# MCU.net
KiCad netlist of a schematic drawn in Altium Designer
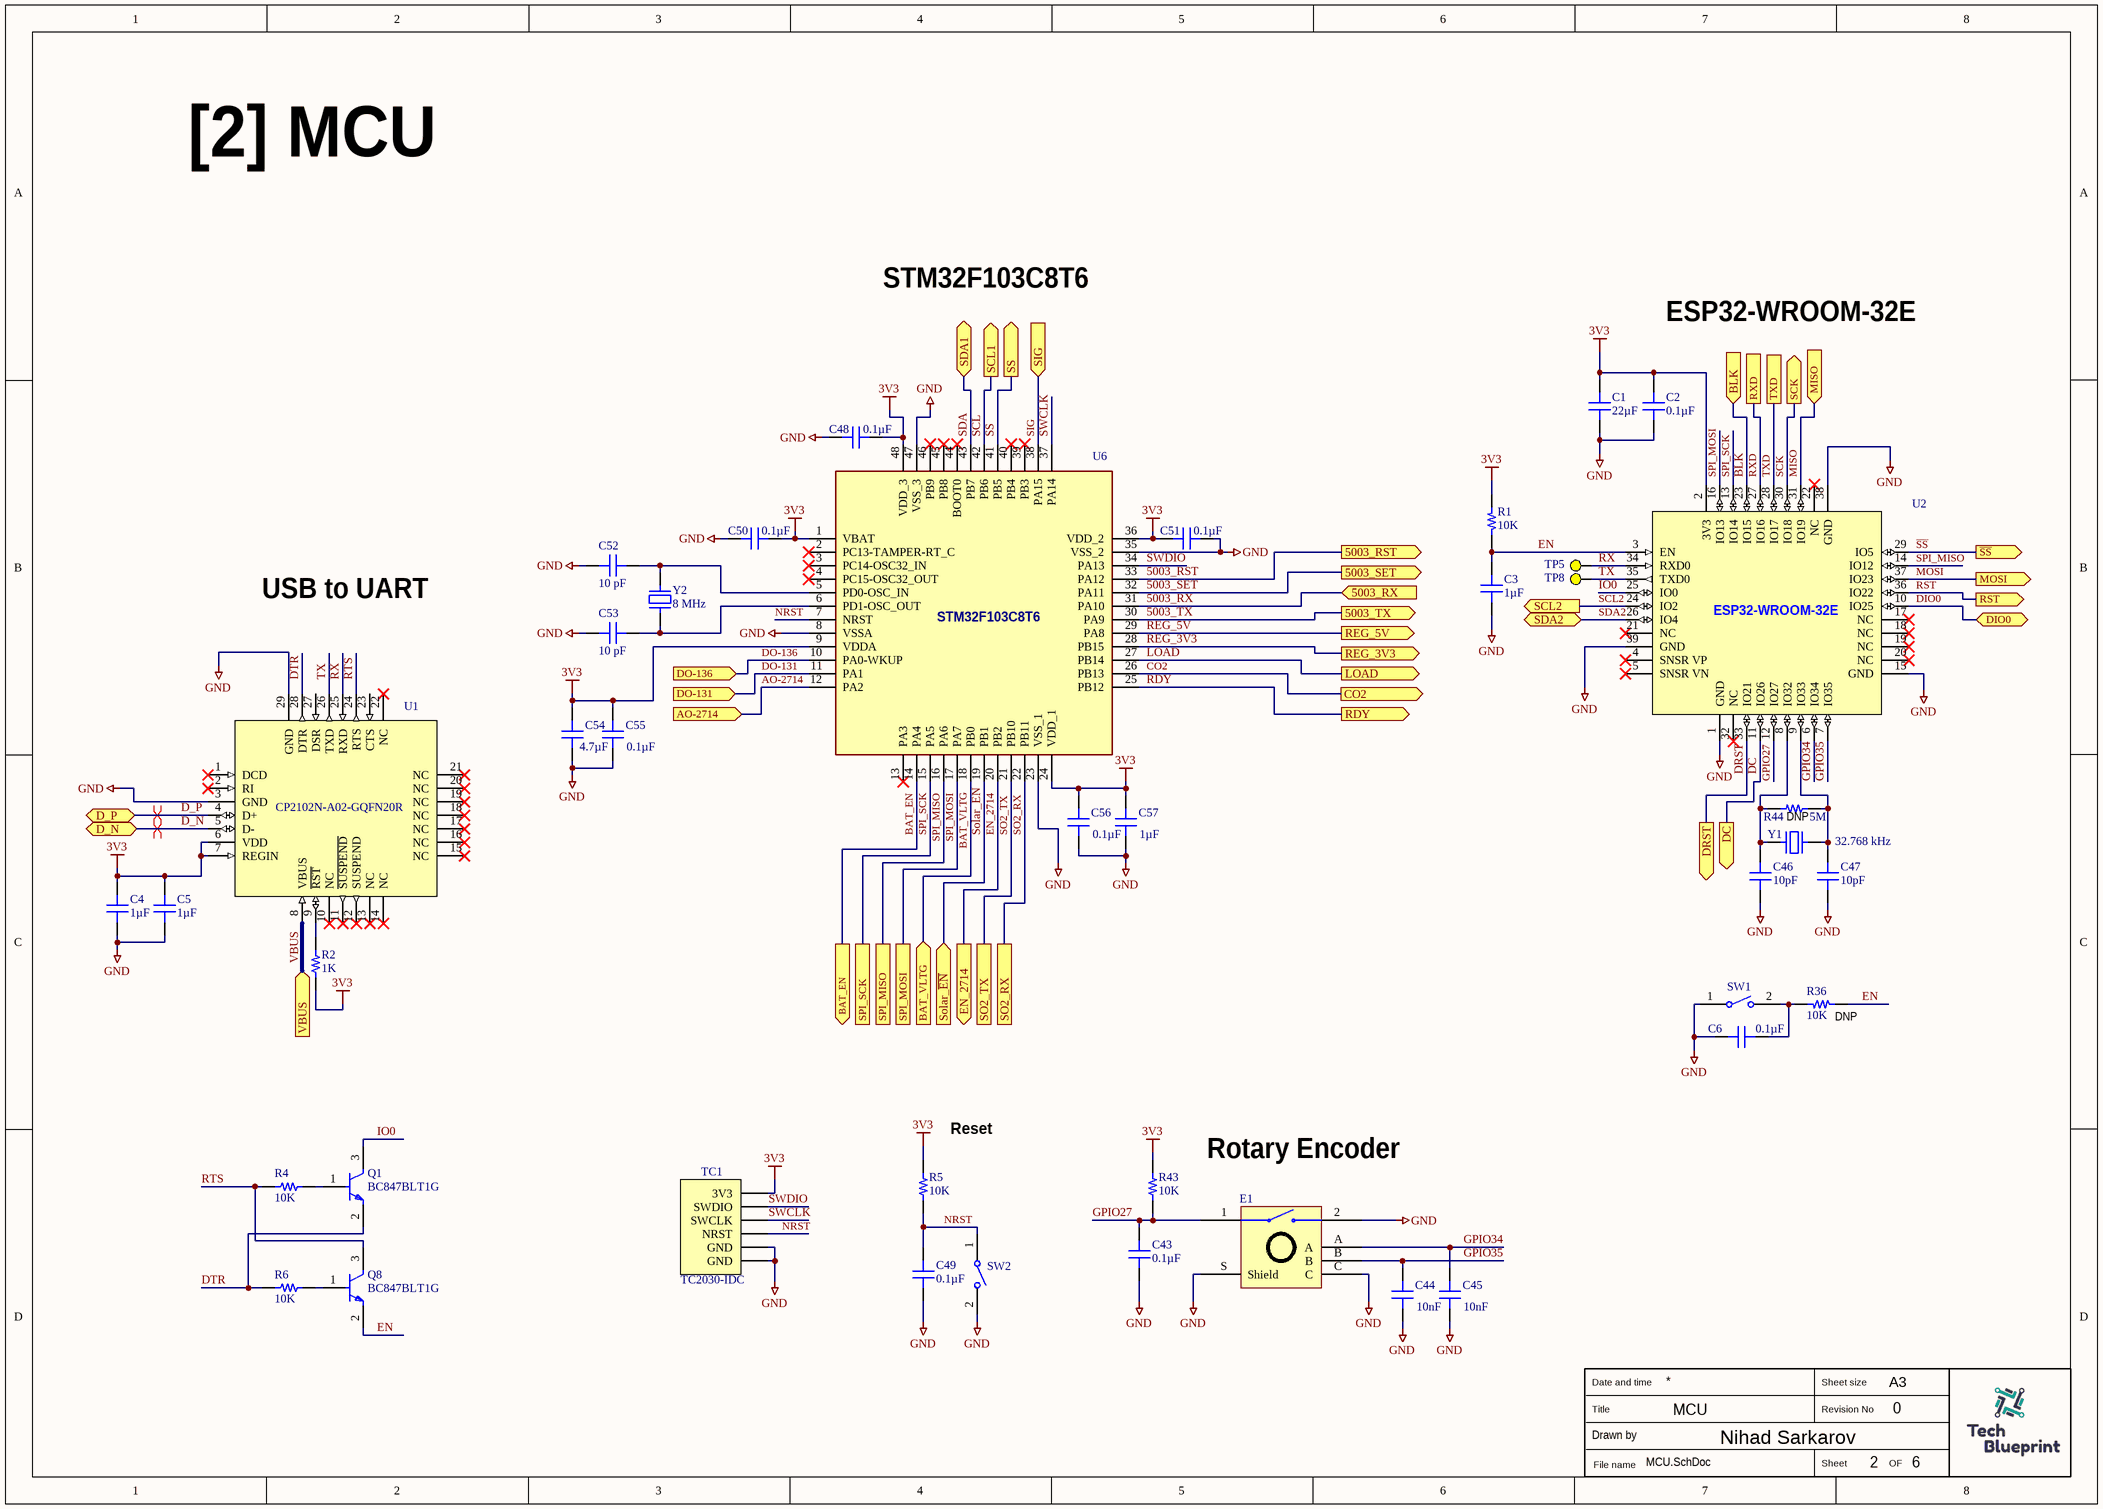
[diagram p0: MCU.SchDoc]

(export (version "E")
  (design (tool "Eeschema 10.0.6"))
  (components
    (comp (ref "C1")
      (value "22µF")
      (footprint "CAP 0805_2012")
      (description "CAP CER 22UF 6.3V X5R 0805")
      (fields
        (field (name "PART NUMBER") "08056D226KAT2A")
        (field (name "CAPACITANCE") "22µF")
        (field (name "MANUFACTURER") "AVX Corporation")
      )
      (libsource (lib "Celestial Altium Library - altium_library") (part "Capacitor"))
    )
    (comp (ref "C2")
      (value "0.1µF")
      (footprint "CAP 0805_2012")
      (description "CAP CER 0.1UF 25V X7R 0805")
      (fields
        (field (name "PART NUMBER") "08053C104KAT4A")
        (field (name "CAPACITANCE") "0.1µF")
        (field (name "MANUFACTURER") "AVX Corporation")
      )
      (libsource (lib "Celestial Altium Library - altium_library") (part "Capacitor"))
    )
    (comp (ref "C3")
      (value "1µF")
      (footprint "CAP 0805_2012")
      (description "CAP CER 1UF 6.3V X5R 0805")
      (fields
        (field (name "PART NUMBER") "LGC26D105MAT2S1")
        (field (name "CAPACITANCE") "1µF")
        (field (name "MANUFACTURER") "AVX Corporation")
      )
      (libsource (lib "Celestial Altium Library - altium_library") (part "Capacitor"))
    )
    (comp (ref "C4")
      (value "1µF")
      (footprint "CAP 0805_2012")
      (description "CAP CER 1UF 6.3V X5R 0805")
      (fields
        (field (name "PART NUMBER") "LGC26D105MAT2S1")
        (field (name "CAPACITANCE") "1µF")
        (field (name "MANUFACTURER") "AVX Corporation")
      )
      (libsource (lib "Celestial Altium Library - altium_library") (part "Capacitor"))
    )
    (comp (ref "C5")
      (value "1µF")
      (footprint "CAP 0805_2012")
      (description "CAP CER 1UF 6.3V X5R 0805")
      (fields
        (field (name "PART NUMBER") "LGC26D105MAT2S1")
        (field (name "CAPACITANCE") "1µF")
        (field (name "MANUFACTURER") "AVX Corporation")
      )
      (libsource (lib "Celestial Altium Library - altium_library") (part "Capacitor"))
    )
    (comp (ref "C6")
      (value "0.1µF")
      (footprint "CAP 0805_2012")
      (description "CAP CER 0.1UF 25V X7R 0805")
      (fields
        (field (name "PART NUMBER") "08053C104KAT4A")
        (field (name "CAPACITANCE") "0.1µF")
        (field (name "MANUFACTURER") "AVX Corporation")
      )
      (libsource (lib "Celestial Altium Library - altium_library") (part "Capacitor"))
    )
    (comp (ref "C43")
      (value "0.1µF")
      (footprint "CAP 0603_1608")
      (description "CAP CER 0.1UF 25V X7R 0603")
      (fields
        (field (name "PART NUMBER") "06033C104K4T4A")
        (field (name "CAPACITANCE") "0.1µF")
        (field (name "MANUFACTURER") "AVX Corporation")
      )
      (libsource (lib "Celestial Altium Library - altium_library") (part "Capacitor"))
    )
    (comp (ref "C44")
      (value "10000 pF")
      (footprint "CAP 0603_1608")
      (description "CAP CER 0603 10NF 16V X7R 10%")
      (fields
        (field (name "PART NUMBER") "C0603C103K4RECAUTO")
        (field (name "CAPACITANCE") "10nF")
        (field (name "MANUFACTURER") "KEMET")
      )
      (libsource (lib "Celestial Altium Library - altium_library") (part "Capacitor"))
    )
    (comp (ref "C45")
      (value "10000 pF")
      (footprint "CAP 0603_1608")
      (description "CAP CER 0603 10NF 16V X7R 10%")
      (fields
        (field (name "PART NUMBER") "C0603C103K4RECAUTO")
        (field (name "CAPACITANCE") "10nF")
        (field (name "MANUFACTURER") "KEMET")
      )
      (libsource (lib "Celestial Altium Library - altium_library") (part "Capacitor"))
    )
    (comp (ref "C46")
      (value "10pF")
      (footprint "CAP 0603_1608")
      (description "CAP CER 10PF 50V NP0 0603")
      (fields
        (field (name "PART NUMBER") "06035A100J4T2A")
        (field (name "CAPACITANCE") "10pF")
        (field (name "MANUFACTURER") "AVX Corporation")
      )
      (libsource (lib "Celestial Altium Library - altium_library") (part "Capacitor"))
    )
    (comp (ref "C47")
      (value "10pF")
      (footprint "CAP 0603_1608")
      (description "CAP CER 10PF 50V NP0 0603")
      (fields
        (field (name "PART NUMBER") "06035A100J4T2A")
        (field (name "CAPACITANCE") "10pF")
        (field (name "MANUFACTURER") "AVX Corporation")
      )
      (libsource (lib "Celestial Altium Library - altium_library") (part "Capacitor"))
    )
    (comp (ref "C48")
      (value "0.1µF")
      (footprint "CAP 0805_2012")
      (description "CAP CER 0.1UF 25V X7R 0805")
      (fields
        (field (name "PART NUMBER") "08053C104K4Z2A")
        (field (name "CAPACITANCE") "0.1µF")
        (field (name "MANUFACTURER") "AVX Corporation")
      )
      (libsource (lib "Celestial Altium Library - altium_library") (part "Capacitor"))
    )
    (comp (ref "C49")
      (value "0.1µF")
      (footprint "CAP 0603_1608")
      (description "CAP CER 0.1UF 25V X7R 0603")
      (fields
        (field (name "PART NUMBER") "06033C104K4T4A")
        (field (name "CAPACITANCE") "0.1µF")
        (field (name "MANUFACTURER") "AVX Corporation")
      )
      (libsource (lib "Celestial Altium Library - altium_library") (part "Capacitor"))
    )
    (comp (ref "C50")
      (value "0.1µF")
      (footprint "CAP 0805_2012")
      (description "CAP CER 0.1UF 25V X7R 0805")
      (fields
        (field (name "PART NUMBER") "08053C104K4Z2A")
        (field (name "CAPACITANCE") "0.1µF")
        (field (name "MANUFACTURER") "AVX Corporation")
      )
      (libsource (lib "Celestial Altium Library - altium_library") (part "Capacitor"))
    )
    (comp (ref "C51")
      (value "0.1µF")
      (footprint "CAP 0805_2012")
      (description "CAP CER 0.1UF 25V X7R 0805")
      (fields
        (field (name "PART NUMBER") "08053C104K4Z2A")
        (field (name "CAPACITANCE") "0.1µF")
        (field (name "MANUFACTURER") "AVX Corporation")
      )
      (libsource (lib "Celestial Altium Library - altium_library") (part "Capacitor"))
    )
    (comp (ref "C52")
      (value "10 pF")
      (footprint "CAP 0603_1608")
      (description "CAP CER 10PF 50V C0G/NP0 0603")
      (fields
        (field (name "PART NUMBER") "500X14N100MV4T")
        (field (name "CAPACITANCE") "10 pF")
        (field (name "MANUFACTURER") "Johanson Dielectrics Inc.")
      )
      (libsource (lib "Celestial Altium Library - altium_library") (part "Capacitor"))
    )
    (comp (ref "C53")
      (value "10 pF")
      (footprint "CAP 0603_1608")
      (description "CAP CER 10PF 50V C0G/NP0 0603")
      (fields
        (field (name "PART NUMBER") "500X14N100MV4T")
        (field (name "CAPACITANCE") "10 pF")
        (field (name "MANUFACTURER") "Johanson Dielectrics Inc.")
      )
      (libsource (lib "Celestial Altium Library - altium_library") (part "Capacitor"))
    )
    (comp (ref "C54")
      (value "4.7µF")
      (footprint "CAP 0805_2012")
      (description "CAP CER 4.7UF 10V X5R 0805")
      (fields
        (field (name "PART NUMBER") "0805ZD475KAT2A")
        (field (name "CAPACITANCE") "4.7µF")
        (field (name "MANUFACTURER") "AVX Corporation")
      )
      (libsource (lib "Celestial Altium Library - altium_library") (part "Capacitor"))
    )
    (comp (ref "C55")
      (value "0.1µF")
      (footprint "CAP 0805_2012")
      (description "CAP CER 0.1UF 25V X7R 0805")
      (fields
        (field (name "PART NUMBER") "08053C104K4Z2A")
        (field (name "CAPACITANCE") "0.1µF")
        (field (name "MANUFACTURER") "AVX Corporation")
      )
      (libsource (lib "Celestial Altium Library - altium_library") (part "Capacitor"))
    )
    (comp (ref "C56")
      (value "0.1µF")
      (footprint "CAP 0805_2012")
      (description "CAP CER 0.1UF 25V X7R 0805")
      (fields
        (field (name "PART NUMBER") "08053C104K4Z2A")
        (field (name "CAPACITANCE") "0.1µF")
        (field (name "MANUFACTURER") "AVX Corporation")
      )
      (libsource (lib "Celestial Altium Library - altium_library") (part "Capacitor"))
    )
    (comp (ref "C57")
      (value "1µF")
      (footprint "CAP 0805_2012")
      (description "CAP CER 1UF 10V X7R 0805")
      (fields
        (field (name "PART NUMBER") "MM05ZC105KCZ2A")
        (field (name "CAPACITANCE") "1µF")
        (field (name "MANUFACTURER") "AVX Corporation")
      )
      (libsource (lib "Celestial Altium Library - altium_library") (part "Capacitor"))
    )
    (comp (ref "E1")
      (value "PEC11R-4315F-S0012")
      (footprint "BOURNS PEC11R-4315F-S0012")
      (description "ROTARY ENCODER MECHANICAL 12PPR")
      (fields (field (name "MANUFACTURER") "Bourns Inc."))
      (libsource (lib "Celestial Altium Library - altium_library") (part "BOURNS PEC11R-4315F-S0012"))
    )
    (comp (ref "Q1")
      (value "BC847BLT1G")
      (footprint "ON_Semi_318-08_MFG")
      (libsource (lib "Altium Content Vault") (part "BC847BLT1G"))
    )
    (comp (ref "Q8")
      (value "BC847BLT1G")
      (footprint "ON_Semi_318-08_MFG")
      (libsource (lib "Altium Content Vault") (part "BC847BLT1G"))
    )
    (comp (ref "R1")
      (value "10K")
      (footprint "RES 0805_2012")
      (description "RES SMD 10K OHM 5% 1/3W 0805")
      (fields
        (field (name "PART NUMBER") "CRGH0805J10K")
        (field (name "MANUFACTURER") "TE Connectivity Passive Product")
      )
      (libsource (lib "Celestial Altium Library - altium_library") (part "Resistor"))
    )
    (comp (ref "R2")
      (value "1K")
      (footprint "RES 0805_2012")
      (description "RES SMD 1K OHM 5% 1/3W 0805")
      (fields
        (field (name "PART NUMBER") "CRGH0805J1K0")
        (field (name "MANUFACTURER") "TE Connectivity Passive Product")
      )
      (libsource (lib "Celestial Altium Library - altium_library") (part "Resistor"))
    )
    (comp (ref "R4")
      (value "10K")
      (footprint "RES 0603_1608")
      (description "RES SMD 10K OHM 5% 1/10W 0603")
      (fields (field (name "PART NUMBER") "CRCW060310K0JNEA") (field (name "MANUFACTURER") "Vishay Dale"))
      (libsource (lib "Celestial Altium Library - altium_library") (part "Resistor"))
    )
    (comp (ref "R5")
      (value "10K")
      (footprint "RES 0603_1608")
      (description "RES SMD 10K OHM 5% 1/10W 0603")
      (fields (field (name "PART NUMBER") "CRCW060310K0JNEA") (field (name "MANUFACTURER") "Vishay Dale"))
      (libsource (lib "Celestial Altium Library - altium_library") (part "Resistor"))
    )
    (comp (ref "R6")
      (value "10K")
      (footprint "RES 0603_1608")
      (description "RES SMD 10K OHM 5% 1/10W 0603")
      (fields (field (name "PART NUMBER") "CRCW060310K0JNEA") (field (name "MANUFACTURER") "Vishay Dale"))
      (libsource (lib "Celestial Altium Library - altium_library") (part "Resistor"))
    )
    (comp (ref "R36")
      (value "10K")
      (footprint "RES 0805_2012")
      (description "RES SMD 10K OHM 5% 1/3W 0805")
      (fields
        (field (name "PART NUMBER") "CRGH0805J10K")
        (field (name "MANUFACTURER") "TE Connectivity Passive Product")
      )
      (libsource (lib "Celestial Altium Library - altium_library") (part "Resistor"))
    )
    (comp (ref "R43")
      (value "10K")
      (footprint "RES 0603_1608")
      (description "RES SMD 10K OHM 5% 1/10W 0603")
      (fields (field (name "PART NUMBER") "CRCW060310K0JNEA") (field (name "MANUFACTURER") "Vishay Dale"))
      (libsource (lib "Celestial Altium Library - altium_library") (part "Resistor"))
    )
    (comp (ref "R44")
      (value "5M")
      (footprint "RES 0603_1608")
      (description "RES SMD 5M OHM 1% 1/10W 0603")
      (fields (field (name "PART NUMBER") "HVC0603T5004FET") (field (name "MANUFACTURER") "Ohmite"))
      (libsource (lib "Celestial Altium Library - altium_library") (part "Resistor"))
    )
    (comp (ref "SW1")
      (value "FSMSMTR")
      (footprint "TECO-FSMSMTR_V")
      (description "FSMSM Push Button Switch, 50 mA, -35 to 85 degC, 2-Pin SMD, RoHS, Tape and Reel")
      (fields (field (name "MANUFACTURER") "TE Connectivity"))
      (libsource (lib "Schlib1") (part "CMP-2000-07501-1"))
    )
    (comp (ref "SW2")
      (value "FSMSMTR")
      (footprint "TECO-FSMSMTR_V")
      (description "FSMSM Push Button Switch, 50 mA, -35 to 85 degC, 2-Pin SMD, RoHS, Tape and Reel")
      (fields (field (name "MANUFACTURER") "TE Connectivity"))
      (libsource (lib "Altium Content Vault") (part "SW-SPST-2_C"))
    )
    (comp (ref "TC1")
      (value "TC2030-IDC")
      (footprint "TC2030-IDC")
      (description "PLUG-OF-NAILS 6-PIN W/ LEGS 8")
      (fields (field (name "MF") "Tag-Connect LLC"))
      (libsource (lib "Schlib1") (part "TC2030-IDC"))
    )
    (comp (ref "TP5")
      (value "Test point")
      (footprint "Test point")
      (description "1mm x 1mm round pad for testing purposes")
      (libsource (lib "Schlib1") (part "Test point"))
    )
    (comp (ref "TP8")
      (value "Test point")
      (footprint "Test point")
      (description "1mm x 1mm round pad for testing purposes")
      (libsource (lib "Schlib1") (part "Test point"))
    )
    (comp (ref "U1")
      (value "CP2102N-A02-GQFN20R")
      (footprint "CP2102:QFN50P500X500X100-29N")
      (description "USB Bridge, USB to UART USB 2.0 UART Interface 20-QFN (3x3)")
      (fields (field (name "MF") "{'manufacturer': u'Silicon Labs'}") (field (name "MP") "CP2102"))
      (libsource (lib "Schlib1") (part "CP2102"))
    )
    (comp (ref "U2")
      (value "ESP32-WROOM-32E(M113EH3200PH3Q0)")
      (footprint "FP-ESP32-WROOM-32E_M113EH-MFG")
      (description "RX TXRX MOD WIFI TRACE ANT SMD")
      (libsource (lib "Schlib1") (part "CMP-194065-000012-1"))
    )
    (comp (ref "U6")
      (value "STM32F103C8T6")
      (footprint "LQFP-48_19.6_393_58X11_SMD")
      (description "ARM® Cortex®-M3 STM32F1 Microcontroller IC 32-Bit 72MHz 64KB (64K x 8) FLASH 48-LQFP (7x7)")
      (fields (field (name "MANUFACTURER") "STMicroelectronics"))
      (libsource (lib "ESTEEMPCBLIB") (part "IC_STM32F103C8T6"))
    )
    (comp (ref "Y1")
      (value "32.768 kHz")
      (footprint "ABRACON ABS07")
      (description "CRYSTAL 32.7680KHZ 7PF SMD")
      (fields (field (name "PART NUMBER") "ABS07-32.768KHZ-7-T") (field (name "MANUFACTURER") "Abracon LLC"))
      (libsource (lib "Celestial Altium Library - altium_library") (part "Abracon Crystal ABS07"))
    )
    (comp (ref "Y2")
      (value "8 MHz")
      (footprint "NDK NX3225GD")
      (description "CRYSTAL 8.0000MHZ 8PF SMD")
      (fields (field (name "PART NUMBER") "CG04874-8M") (field (name "MANUFACTURER") "NDK America, Inc."))
      (libsource (lib "Celestial Altium Library - altium_library") (part "NDK NX3225GD"))
    )
  )
  (nets
    (net (code "1") (name "/5003_RST") (class "Default")
      (node (ref "U6") (pin "33") (pinfunction "PA12_33") (pintype "passive"))
    )
    (net (code "2") (name "/5003_RX") (class "Default")
      (node (ref "U6") (pin "31") (pinfunction "PA10_31") (pintype "passive"))
    )
    (net (code "3") (name "/5003_SET") (class "Default")
      (node (ref "U6") (pin "32") (pinfunction "PA11_32") (pintype "passive"))
    )
    (net (code "4") (name "/5003_TX") (class "Default")
      (node (ref "U6") (pin "30") (pinfunction "PA9_30") (pintype "passive"))
    )
    (net (code "5") (name "/AO-2714") (class "Default")
      (node (ref "U6") (pin "12") (pinfunction "PA2_12") (pintype "passive"))
    )
    (net (code "6") (name "/BAT_EN") (class "Default")
      (node (ref "U6") (pin "14") (pinfunction "PA4_14") (pintype "passive"))
    )
    (net (code "7") (name "/BAT_VLTG") (class "Default")
      (node (ref "U6") (pin "18") (pinfunction "PB0_18") (pintype "passive"))
    )
    (net (code "8") (name "/BLK") (class "Default")
      (node (ref "U2") (pin "23") (pinfunction "IO15_23") (pintype "bidirectional"))
    )
    (net (code "9") (name "/CO2") (class "Default")
      (node (ref "U6") (pin "26") (pinfunction "PB13_26") (pintype "passive"))
    )
    (net (code "10") (name "/DC") (class "Default")
      (node (ref "U2") (pin "11") (pinfunction "IO26_11") (pintype "bidirectional"))
    )
    (net (code "11") (name "/DIO0") (class "Default")
      (node (ref "U2") (pin "10") (pinfunction "IO25_10") (pintype "bidirectional"))
    )
    (net (code "12") (name "/DO-131") (class "Default")
      (node (ref "U6") (pin "11") (pinfunction "PA1_11") (pintype "passive"))
    )
    (net (code "13") (name "/DO-136") (class "Default")
      (node (ref "U6") (pin "10") (pinfunction "PA0-WKUP_10") (pintype "passive"))
    )
    (net (code "14") (name "/DRST") (class "Default")
      (node (ref "U2") (pin "33") (pinfunction "IO21_33") (pintype "bidirectional"))
    )
    (net (code "15") (name "/DTR") (class "Default")
      (node (ref "Q1") (pin "2") (pinfunction "E_2") (pintype "passive"))
      (node (ref "R6") (pin "2") (pinfunction "2_2") (pintype "passive"))
      (node (ref "U1") (pin "28") (pinfunction "DTR_28") (pintype "output"))
    )
    (net (code "16") (name "/D_N") (class "Default")
      (node (ref "U1") (pin "5") (pinfunction "D-_5") (pintype "bidirectional"))
    )
    (net (code "17") (name "/D_P") (class "Default")
      (node (ref "U1") (pin "4") (pinfunction "D+_4") (pintype "bidirectional"))
    )
    (net (code "18") (name "/EN") (class "Default")
      (node (ref "C3") (pin "2") (pinfunction "2_2") (pintype "passive"))
      (node (ref "Q8") (pin "2") (pinfunction "E_2") (pintype "passive"))
      (node (ref "R1") (pin "1") (pinfunction "1_1") (pintype "passive"))
      (node (ref "R36") (pin "1") (pinfunction "1_1") (pintype "passive"))
      (node (ref "U2") (pin "3") (pinfunction "EN_3") (pintype "input"))
    )
    (net (code "19") (name "/EN_2714") (class "Default")
      (node (ref "U6") (pin "20") (pinfunction "PB2_20") (pintype "passive"))
    )
    (net (code "20") (name "/GPIO27") (class "Default")
      (node (ref "C43") (pin "2") (pinfunction "2_2") (pintype "passive"))
      (node (ref "E1") (pin "1") (pinfunction "1_1") (pintype "passive"))
      (node (ref "R43") (pin "1") (pinfunction "1_1") (pintype "passive"))
      (node (ref "U2") (pin "12") (pinfunction "IO27_12") (pintype "bidirectional"))
    )
    (net (code "21") (name "/GPIO34") (class "Default")
      (node (ref "C45") (pin "2") (pinfunction "2_2") (pintype "passive"))
      (node (ref "E1") (pin "A") (pinfunction "A_A") (pintype "passive"))
      (node (ref "U2") (pin "6") (pinfunction "IO34_6") (pintype "bidirectional"))
    )
    (net (code "22") (name "/GPIO35") (class "Default")
      (node (ref "C44") (pin "2") (pinfunction "2_2") (pintype "passive"))
      (node (ref "E1") (pin "B") (pinfunction "B_B") (pintype "passive"))
      (node (ref "U2") (pin "7") (pinfunction "IO35_7") (pintype "bidirectional"))
    )
    (net (code "23") (name "/IO0") (class "Default")
      (node (ref "Q1") (pin "3") (pinfunction "C_3") (pintype "passive"))
      (node (ref "U2") (pin "25") (pinfunction "IO0_25") (pintype "bidirectional"))
    )
    (net (code "24") (name "/LOAD") (class "Default")
      (node (ref "U6") (pin "27") (pinfunction "PB14_27") (pintype "passive"))
    )
    (net (code "25") (name "/MISO") (class "Default")
      (node (ref "U2") (pin "31") (pinfunction "IO19_31") (pintype "bidirectional"))
    )
    (net (code "26") (name "/MOSI") (class "Default")
      (node (ref "U2") (pin "37") (pinfunction "IO23_37") (pintype "bidirectional"))
    )
    (net (code "27") (name "/NRST") (class "Default")
      (node (ref "C49") (pin "2") (pinfunction "2_2") (pintype "passive"))
      (node (ref "R5") (pin "1") (pinfunction "1_1") (pintype "passive"))
      (node (ref "SW2") (pin "1") (pinfunction "1_1") (pintype "passive"))
      (node (ref "TC1") (pin "5") (pinfunction "NRST_5") (pintype "passive"))
      (node (ref "U6") (pin "7") (pinfunction "NRST_7") (pintype "passive"))
    )
    (net (code "28") (name "/RDY") (class "Default")
      (node (ref "U6") (pin "25") (pinfunction "PB12_25") (pintype "passive"))
    )
    (net (code "29") (name "/REG_3V3") (class "Default")
      (node (ref "U6") (pin "28") (pinfunction "PB15_28") (pintype "passive"))
    )
    (net (code "30") (name "/REG_5V") (class "Default")
      (node (ref "U6") (pin "29") (pinfunction "PA8_29") (pintype "passive"))
    )
    (net (code "31") (name "/RST") (class "Default")
      (node (ref "U2") (pin "36") (pinfunction "IO22_36") (pintype "bidirectional"))
    )
    (net (code "32") (name "/RTS") (class "Default")
      (node (ref "Q8") (pin "3") (pinfunction "C_3") (pintype "passive"))
      (node (ref "R4") (pin "2") (pinfunction "2_2") (pintype "passive"))
      (node (ref "U1") (pin "24") (pinfunction "RTS_24") (pintype "output"))
    )
    (net (code "33") (name "/RX") (class "Default")
      (node (ref "TP5") (pin "1") (pinfunction "1_1") (pintype "passive"))
      (node (ref "U1") (pin "25") (pinfunction "RXD_25") (pintype "input"))
      (node (ref "U2") (pin "34") (pinfunction "RXD0_34") (pintype "input"))
    )
    (net (code "34") (name "/RXD") (class "Default")
      (node (ref "U2") (pin "27") (pinfunction "IO16_27") (pintype "bidirectional"))
    )
    (net (code "35") (name "/SCK") (class "Default")
      (node (ref "U2") (pin "30") (pinfunction "IO18_30") (pintype "bidirectional"))
    )
    (net (code "36") (name "/SCL") (class "Default")
      (node (ref "U6") (pin "42") (pinfunction "PB6_42") (pintype "passive"))
    )
    (net (code "37") (name "/SCL2") (class "Default")
      (node (ref "U2") (pin "24") (pinfunction "IO2_24") (pintype "bidirectional"))
    )
    (net (code "38") (name "/SDA") (class "Default")
      (node (ref "U6") (pin "43") (pinfunction "PB7_43") (pintype "passive"))
    )
    (net (code "39") (name "/SDA2") (class "Default")
      (node (ref "U2") (pin "26") (pinfunction "IO4_26") (pintype "bidirectional"))
    )
    (net (code "40") (name "/SIG") (class "Default")
      (node (ref "U6") (pin "38") (pinfunction "PA15_38") (pintype "passive"))
    )
    (net (code "41") (name "/SO2_RX") (class "Default")
      (node (ref "U6") (pin "22") (pinfunction "PB11_22") (pintype "passive"))
    )
    (net (code "42") (name "/SO2_TX") (class "Default")
      (node (ref "U6") (pin "21") (pinfunction "PB10_21") (pintype "passive"))
    )
    (net (code "43") (name "/SPI_MISO") (class "Default")
      (node (ref "U2") (pin "14") (pinfunction "IO12_14") (pintype "bidirectional"))
      (node (ref "U6") (pin "16") (pinfunction "PA6_16") (pintype "passive"))
    )
    (net (code "44") (name "/SPI_MOSI") (class "Default")
      (node (ref "U2") (pin "16") (pinfunction "IO13_16") (pintype "bidirectional"))
      (node (ref "U6") (pin "17") (pinfunction "PA7_17") (pintype "passive"))
    )
    (net (code "45") (name "/SPI_SCK") (class "Default")
      (node (ref "U2") (pin "13") (pinfunction "IO14_13") (pintype "bidirectional"))
      (node (ref "U6") (pin "15") (pinfunction "PA5_15") (pintype "passive"))
    )
    (net (code "46") (name "/SS") (class "Default")
      (node (ref "U6") (pin "41") (pinfunction "PB5_41") (pintype "passive"))
    )
    (net (code "47") (name "/SWCLK") (class "Default")
      (node (ref "TC1") (pin "3") (pinfunction "SWCLK_3") (pintype "passive"))
      (node (ref "U6") (pin "37") (pinfunction "PA14_37") (pintype "passive"))
    )
    (net (code "48") (name "/SWDIO") (class "Default")
      (node (ref "TC1") (pin "1") (pinfunction "SWDIO_1") (pintype "passive"))
      (node (ref "U6") (pin "34") (pinfunction "PA13_34") (pintype "passive"))
    )
    (net (code "49") (name "/Solar_~{EN}") (class "Default")
      (node (ref "U6") (pin "19") (pinfunction "PB1_19") (pintype "passive"))
    )
    (net (code "50") (name "/TX") (class "Default")
      (node (ref "TP8") (pin "1") (pinfunction "1_1") (pintype "passive"))
      (node (ref "U1") (pin "26") (pinfunction "TXD_26") (pintype "output"))
      (node (ref "U2") (pin "35") (pinfunction "TXD0_35") (pintype "output"))
    )
    (net (code "51") (name "/TXD") (class "Default")
      (node (ref "U2") (pin "28") (pinfunction "IO17_28") (pintype "bidirectional"))
    )
    (net (code "52") (name "/VBUS") (class "Default")
      (node (ref "U1") (pin "8") (pinfunction "VBUS_8") (pintype "input"))
    )
    (net (code "53") (name "/~{SS}") (class "Default")
      (node (ref "U2") (pin "29") (pinfunction "IO5_29") (pintype "bidirectional"))
    )
    (net (code "54") (name "3V3") (class "Default")
      (node (ref "C1") (pin "2") (pinfunction "2_2") (pintype "passive"))
      (node (ref "C2") (pin "2") (pinfunction "2_2") (pintype "passive"))
      (node (ref "C4") (pin "2") (pinfunction "2_2") (pintype "passive"))
      (node (ref "C48") (pin "2") (pinfunction "2_2") (pintype "passive"))
      (node (ref "C5") (pin "2") (pinfunction "2_2") (pintype "passive"))
      (node (ref "C50") (pin "2") (pinfunction "2_2") (pintype "passive"))
      (node (ref "C51") (pin "1") (pinfunction "1_1") (pintype "passive"))
      (node (ref "C54") (pin "2") (pinfunction "2_2") (pintype "passive"))
      (node (ref "C55") (pin "2") (pinfunction "2_2") (pintype "passive"))
      (node (ref "C56") (pin "2") (pinfunction "2_2") (pintype "passive"))
      (node (ref "C57") (pin "2") (pinfunction "2_2") (pintype "passive"))
      (node (ref "R1") (pin "2") (pinfunction "2_2") (pintype "passive"))
      (node (ref "R2") (pin "1") (pinfunction "1_1") (pintype "passive"))
      (node (ref "R43") (pin "2") (pinfunction "2_2") (pintype "passive"))
      (node (ref "R5") (pin "2") (pinfunction "2_2") (pintype "passive"))
      (node (ref "TC1") (pin "6") (pinfunction "3V3_6") (pintype "passive"))
      (node (ref "U1") (pin "6") (pinfunction "VDD_6") (pintype "power_in"))
      (node (ref "U1") (pin "7") (pinfunction "REGIN_7") (pintype "input"))
      (node (ref "U2") (pin "2") (pinfunction "3V3_2") (pintype "power_in"))
      (node (ref "U6") (pin "1") (pinfunction "VBAT_1") (pintype "passive"))
      (node (ref "U6") (pin "24") (pinfunction "VDD_1_24") (pintype "passive"))
      (node (ref "U6") (pin "36") (pinfunction "VDD_2_36") (pintype "passive"))
      (node (ref "U6") (pin "48") (pinfunction "VDD_3_48") (pintype "passive"))
      (node (ref "U6") (pin "9") (pinfunction "VDDA_9") (pintype "passive"))
    )
    (net (code "55") (name "GND") (class "Default")
      (node (ref "C1") (pin "1") (pinfunction "1_1") (pintype "passive"))
      (node (ref "C2") (pin "1") (pinfunction "1_1") (pintype "passive"))
      (node (ref "C3") (pin "1") (pinfunction "1_1") (pintype "passive"))
      (node (ref "C4") (pin "1") (pinfunction "1_1") (pintype "passive"))
      (node (ref "C43") (pin "1") (pinfunction "1_1") (pintype "passive"))
      (node (ref "C44") (pin "1") (pinfunction "1_1") (pintype "passive"))
      (node (ref "C45") (pin "1") (pinfunction "1_1") (pintype "passive"))
      (node (ref "C46") (pin "1") (pinfunction "1_1") (pintype "passive"))
      (node (ref "C47") (pin "1") (pinfunction "1_1") (pintype "passive"))
      (node (ref "C48") (pin "1") (pinfunction "1_1") (pintype "passive"))
      (node (ref "C49") (pin "1") (pinfunction "1_1") (pintype "passive"))
      (node (ref "C5") (pin "1") (pinfunction "1_1") (pintype "passive"))
      (node (ref "C50") (pin "1") (pinfunction "1_1") (pintype "passive"))
      (node (ref "C51") (pin "2") (pinfunction "2_2") (pintype "passive"))
      (node (ref "C52") (pin "1") (pinfunction "1_1") (pintype "passive"))
      (node (ref "C53") (pin "1") (pinfunction "1_1") (pintype "passive"))
      (node (ref "C54") (pin "1") (pinfunction "1_1") (pintype "passive"))
      (node (ref "C55") (pin "1") (pinfunction "1_1") (pintype "passive"))
      (node (ref "C56") (pin "1") (pinfunction "1_1") (pintype "passive"))
      (node (ref "C57") (pin "1") (pinfunction "1_1") (pintype "passive"))
      (node (ref "C6") (pin "2") (pinfunction "2_2") (pintype "passive"))
      (node (ref "E1") (pin "2") (pinfunction "2_2") (pintype "passive"))
      (node (ref "E1") (pin "C") (pinfunction "C_C") (pintype "passive"))
      (node (ref "E1") (pin "S") (pinfunction "Shield_S") (pintype "passive"))
      (node (ref "SW1") (pin "1") (pinfunction "1_1") (pintype "passive"))
      (node (ref "SW2") (pin "2") (pinfunction "2_2") (pintype "passive"))
      (node (ref "TC1") (pin "2") (pinfunction "GND_2") (pintype "passive"))
      (node (ref "TC1") (pin "4") (pinfunction "GND_4") (pintype "passive"))
      (node (ref "U1") (pin "29") (pinfunction "GND_29") (pintype "power_in"))
      (node (ref "U1") (pin "3") (pinfunction "GND_3") (pintype "passive"))
      (node (ref "U2") (pin "1") (pinfunction "GND_1") (pintype "passive"))
      (node (ref "U2") (pin "15") (pinfunction "GND_15") (pintype "power_in"))
      (node (ref "U2") (pin "38") (pinfunction "GND_38") (pintype "power_in"))
      (node (ref "U2") (pin "39") (pinfunction "GND_39") (pintype "passive"))
      (node (ref "U6") (pin "23") (pinfunction "VSS_1_23") (pintype "passive"))
      (node (ref "U6") (pin "35") (pinfunction "VSS_2_35") (pintype "passive"))
      (node (ref "U6") (pin "47") (pinfunction "VSS_3_47") (pintype "passive"))
      (node (ref "U6") (pin "8") (pinfunction "VSSA_8") (pintype "passive"))
    )
    (net (code "56") (name "Net-(C6-Pad1)") (class "Default")
      (node (ref "C6") (pin "1") (pinfunction "1_1") (pintype "passive"))
      (node (ref "R36") (pin "2") (pinfunction "2_2") (pintype "passive"))
      (node (ref "SW1") (pin "2") (pinfunction "2_2") (pintype "passive"))
    )
    (net (code "57") (name "Net-(Q1-B)") (class "Default")
      (node (ref "Q1") (pin "1") (pinfunction "B_1") (pintype "passive"))
      (node (ref "R4") (pin "1") (pinfunction "1_1") (pintype "passive"))
    )
    (net (code "58") (name "Net-(Q8-B)") (class "Default")
      (node (ref "Q8") (pin "1") (pinfunction "B_1") (pintype "passive"))
      (node (ref "R6") (pin "1") (pinfunction "1_1") (pintype "passive"))
    )
    (net (code "59") (name "Net-(U1-~{RST})") (class "Default")
      (node (ref "R2") (pin "2") (pinfunction "2_2") (pintype "passive"))
      (node (ref "U1") (pin "9") (pinfunction "~{RST}_9") (pintype "bidirectional"))
    )
    (net (code "60") (name "Net-(U2-IO32)") (class "Default")
      (node (ref "C46") (pin "2") (pinfunction "2_2") (pintype "passive"))
      (node (ref "R44") (pin "1") (pinfunction "1_1") (pintype "passive"))
      (node (ref "U2") (pin "8") (pinfunction "IO32_8") (pintype "bidirectional"))
      (node (ref "Y1") (pin "2") (pinfunction "2_2") (pintype "passive"))
    )
    (net (code "61") (name "Net-(U2-IO33)") (class "Default")
      (node (ref "C47") (pin "2") (pinfunction "2_2") (pintype "passive"))
      (node (ref "R44") (pin "2") (pinfunction "2_2") (pintype "passive"))
      (node (ref "U2") (pin "9") (pinfunction "IO33_9") (pintype "bidirectional"))
      (node (ref "Y1") (pin "1") (pinfunction "1_1") (pintype "passive"))
    )
    (net (code "62") (name "Net-(U6-PD0-OSC_IN)") (class "Default")
      (node (ref "C52") (pin "2") (pinfunction "2_2") (pintype "passive"))
      (node (ref "U6") (pin "5") (pinfunction "PD0-OSC_IN_5") (pintype "passive"))
      (node (ref "Y2") (pin "2") (pinfunction "2_2") (pintype "passive"))
    )
    (net (code "63") (name "Net-(U6-PD1-OSC_OUT)") (class "Default")
      (node (ref "C53") (pin "2") (pinfunction "2_2") (pintype "passive"))
      (node (ref "U6") (pin "6") (pinfunction "PD1-OSC_OUT_6") (pintype "passive"))
      (node (ref "Y2") (pin "1") (pinfunction "1_1") (pintype "passive"))
    )
    (net (code "64") (name "unconnected-(U1-CTS-Pad23)") (class "Default")
      (node (ref "U1") (pin "23") (pinfunction "CTS_23") (pintype "input"))
    )
    (net (code "65") (name "unconnected-(U1-DCD-Pad1)") (class "Default")
      (node (ref "U1") (pin "1") (pinfunction "DCD_1") (pintype "input+no_connect"))
    )
    (net (code "66") (name "unconnected-(U1-DSR-Pad27)") (class "Default")
      (node (ref "U1") (pin "27") (pinfunction "DSR_27") (pintype "input"))
    )
    (net (code "67") (name "unconnected-(U1-NC-Pad10)") (class "Default")
      (node (ref "U1") (pin "10") (pinfunction "NC_10") (pintype "passive+no_connect"))
    )
    (net (code "68") (name "unconnected-(U1-NC-Pad13)") (class "Default")
      (node (ref "U1") (pin "13") (pinfunction "NC_13") (pintype "passive+no_connect"))
    )
    (net (code "69") (name "unconnected-(U1-NC-Pad14)") (class "Default")
      (node (ref "U1") (pin "14") (pinfunction "NC_14") (pintype "passive+no_connect"))
    )
    (net (code "70") (name "unconnected-(U1-NC-Pad15)") (class "Default")
      (node (ref "U1") (pin "15") (pinfunction "NC_15") (pintype "passive+no_connect"))
    )
    (net (code "71") (name "unconnected-(U1-NC-Pad16)") (class "Default")
      (node (ref "U1") (pin "16") (pinfunction "NC_16") (pintype "passive+no_connect"))
    )
    (net (code "72") (name "unconnected-(U1-NC-Pad17)") (class "Default")
      (node (ref "U1") (pin "17") (pinfunction "NC_17") (pintype "passive+no_connect"))
    )
    (net (code "73") (name "unconnected-(U1-NC-Pad18)") (class "Default")
      (node (ref "U1") (pin "18") (pinfunction "NC_18") (pintype "passive+no_connect"))
    )
    (net (code "74") (name "unconnected-(U1-NC-Pad19)") (class "Default")
      (node (ref "U1") (pin "19") (pinfunction "NC_19") (pintype "passive+no_connect"))
    )
    (net (code "75") (name "unconnected-(U1-NC-Pad20)") (class "Default")
      (node (ref "U1") (pin "20") (pinfunction "NC_20") (pintype "passive+no_connect"))
    )
    (net (code "76") (name "unconnected-(U1-NC-Pad21)") (class "Default")
      (node (ref "U1") (pin "21") (pinfunction "NC_21") (pintype "passive+no_connect"))
    )
    (net (code "77") (name "unconnected-(U1-NC-Pad22)") (class "Default")
      (node (ref "U1") (pin "22") (pinfunction "NC_22") (pintype "passive+no_connect"))
    )
    (net (code "78") (name "unconnected-(U1-RI-Pad2)") (class "Default")
      (node (ref "U1") (pin "2") (pinfunction "RI_2") (pintype "input+no_connect"))
    )
    (net (code "79") (name "unconnected-(U1-SUSPEND-Pad12)") (class "Default")
      (node (ref "U1") (pin "12") (pinfunction "SUSPEND_12") (pintype "output+no_connect"))
    )
    (net (code "80") (name "unconnected-(U1-~{SUSPEND}-Pad11)") (class "Default")
      (node (ref "U1") (pin "11") (pinfunction "~{SUSPEND}_11") (pintype "output+no_connect"))
    )
    (net (code "81") (name "unconnected-(U2-NC-Pad17)") (class "Default")
      (node (ref "U2") (pin "17") (pinfunction "NC_17") (pintype "passive+no_connect"))
    )
    (net (code "82") (name "unconnected-(U2-NC-Pad18)") (class "Default")
      (node (ref "U2") (pin "18") (pinfunction "NC_18") (pintype "passive+no_connect"))
    )
    (net (code "83") (name "unconnected-(U2-NC-Pad19)") (class "Default")
      (node (ref "U2") (pin "19") (pinfunction "NC_19") (pintype "passive+no_connect"))
    )
    (net (code "84") (name "unconnected-(U2-NC-Pad20)") (class "Default")
      (node (ref "U2") (pin "20") (pinfunction "NC_20") (pintype "passive+no_connect"))
    )
    (net (code "85") (name "unconnected-(U2-NC-Pad21)") (class "Default")
      (node (ref "U2") (pin "21") (pinfunction "NC_21") (pintype "passive+no_connect"))
    )
    (net (code "86") (name "unconnected-(U2-NC-Pad22)") (class "Default")
      (node (ref "U2") (pin "22") (pinfunction "NC_22") (pintype "passive+no_connect"))
    )
    (net (code "87") (name "unconnected-(U2-NC-Pad32)") (class "Default")
      (node (ref "U2") (pin "32") (pinfunction "NC_32") (pintype "passive+no_connect"))
    )
    (net (code "88") (name "unconnected-(U2-SNSR_VN-Pad5)") (class "Default")
      (node (ref "U2") (pin "5") (pinfunction "SNSR_VN_5") (pintype "passive+no_connect"))
    )
    (net (code "89") (name "unconnected-(U2-SNSR_VP-Pad4)") (class "Default")
      (node (ref "U2") (pin "4") (pinfunction "SNSR_VP_4") (pintype "passive+no_connect"))
    )
    (net (code "90") (name "unconnected-(U6-BOOT0-Pad44)") (class "Default")
      (node (ref "U6") (pin "44") (pinfunction "BOOT0_44") (pintype "passive+no_connect"))
    )
    (net (code "91") (name "unconnected-(U6-PA3-Pad13)") (class "Default")
      (node (ref "U6") (pin "13") (pinfunction "PA3_13") (pintype "passive+no_connect"))
    )
    (net (code "92") (name "unconnected-(U6-PB3-Pad39)") (class "Default")
      (node (ref "U6") (pin "39") (pinfunction "PB3_39") (pintype "passive+no_connect"))
    )
    (net (code "93") (name "unconnected-(U6-PB4-Pad40)") (class "Default")
      (node (ref "U6") (pin "40") (pinfunction "PB4_40") (pintype "passive+no_connect"))
    )
    (net (code "94") (name "unconnected-(U6-PB8-Pad45)") (class "Default")
      (node (ref "U6") (pin "45") (pinfunction "PB8_45") (pintype "passive+no_connect"))
    )
    (net (code "95") (name "unconnected-(U6-PB9-Pad46)") (class "Default")
      (node (ref "U6") (pin "46") (pinfunction "PB9_46") (pintype "passive+no_connect"))
    )
    (net (code "96") (name "unconnected-(U6-PC13-TAMPER-RT_C-Pad2)") (class "Default")
      (node (ref "U6") (pin "2") (pinfunction "PC13-TAMPER-RT_C_2") (pintype "passive+no_connect"))
    )
    (net (code "97") (name "unconnected-(U6-PC14-OSC32_IN-Pad3)") (class "Default")
      (node (ref "U6") (pin "3") (pinfunction "PC14-OSC32_IN_3") (pintype "passive+no_connect"))
    )
    (net (code "98") (name "unconnected-(U6-PC15-OSC32_OUT-Pad4)") (class "Default")
      (node (ref "U6") (pin "4") (pinfunction "PC15-OSC32_OUT_4") (pintype "passive+no_connect"))
    )
  )
)
